# Easel_circuit_samples.net
KiCad netlist of a schematic drawn in EAGLE
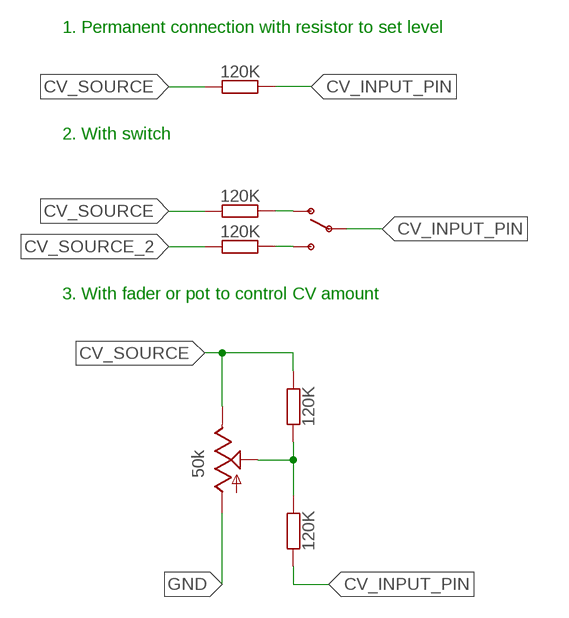
[diagram p0: schematic, sheet 1]
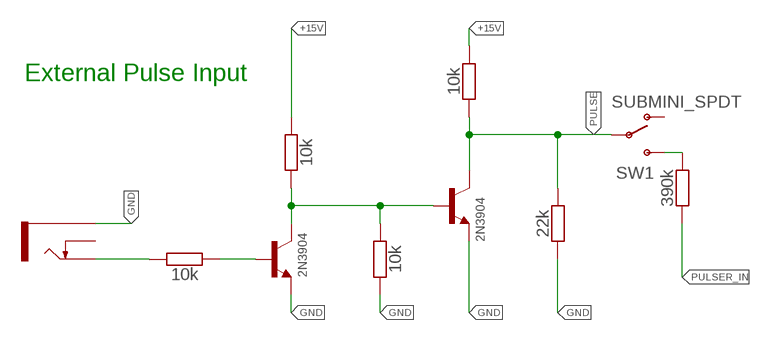
[diagram p1: schematic, sheet 2]

(export (version "E")
  (design (tool "Eeschema 10.0.6"))
  (components
    (comp (ref "Q1")
      (value "2N3904")
      (footprint "eagle-import:SC70-6")
      (libsource (lib "eagle-import") (part "TRANS_NPN_DUAL-MBT3904DW1T1"))
    )
    (comp (ref "R6")
      (value "10k")
      (footprint "eagle-import:C0603")
      (libsource (lib "eagle-import") (part "RESISTOR-0603"))
    )
    (comp (ref "R7")
      (value "10k")
      (footprint "eagle-import:C0603")
      (libsource (lib "eagle-import") (part "RESISTOR-0603"))
    )
    (comp (ref "R8")
      (value "10k")
      (footprint "eagle-import:C0603")
      (libsource (lib "eagle-import") (part "RESISTOR-0603"))
    )
    (comp (ref "R9")
      (value "10k")
      (footprint "eagle-import:C0603")
      (libsource (lib "eagle-import") (part "RESISTOR-0603"))
    )
    (comp (ref "R10")
      (value "22k")
      (footprint "eagle-import:C0603")
      (libsource (lib "eagle-import") (part "RESISTOR-0603"))
    )
    (comp (ref "R11")
      (value "390k")
      (footprint "eagle-import:C0603")
      (libsource (lib "eagle-import") (part "RESISTOR-0603"))
    )
    (comp (ref "SW1")
      (value "SUBMINI_SPDT")
      (footprint "eagle-import:SUBMINI_TOGGLE")
      (libsource (lib "eagle-import") (part "SUBMINI_SPDT"))
    )
    (comp (ref "U1")
      (value "THONKICONNNEW")
      (footprint "eagle-import:WQP-PJ301M-12_JACK")
      (libsource (lib "eagle-import") (part "THONKICONNNEW"))
    )
    (comp (ref "R1")
      (value "120K")
      (footprint "eagle-import:C0603")
      (libsource (lib "eagle-import") (part "RESISTOR-0603"))
    )
    (comp (ref "R2")
      (value "120K")
      (footprint "eagle-import:C0603")
      (libsource (lib "eagle-import") (part "RESISTOR-0603"))
    )
    (comp (ref "R3")
      (value "120K")
      (footprint "eagle-import:C0603")
      (libsource (lib "eagle-import") (part "RESISTOR-0603"))
    )
    (comp (ref "R4")
      (value "120K")
      (footprint "eagle-import:C0603")
      (libsource (lib "eagle-import") (part "RESISTOR-0603"))
    )
    (comp (ref "R5")
      (value "120K")
      (footprint "eagle-import:C0603")
      (libsource (lib "eagle-import") (part "RESISTOR-0603"))
    )
    (comp (ref "S1")
      (value "GRAYHILL_34E_SMD_TOGGLE")
      (footprint "eagle-import:34EWMSP12M6RT")
      (fields
        (field (name "ARROW_PART_NUMBER") "34EWMSP12M6RT")
        (field (name "MOUSER_PART_NUMBER") "706-34EWMSP12M6RT")
      )
      (libsource (lib "eagle-import") (part "GRAYHILL_34E_SMD_TOGGLE"))
    )
    (comp (ref "VR1")
      (value "50k")
      (footprint "eagle-import:9MM_SNAP-IN_POT")
      (libsource (lib "eagle-import") (part "9MM_SNAP-IN_POT_"))
    )
  )
  (nets
    (net (code "1") (name "+15V") (class "Default")
      (node (ref "R7") (pin "2") (pinfunction "2_2") (pintype "passive"))
      (node (ref "R9") (pin "1") (pinfunction "1_1") (pintype "passive"))
    )
    (net (code "2") (name "CV_INPUT_PIN") (class "Default")
      (node (ref "R2") (pin "1") (pinfunction "1_1") (pintype "passive"))
      (node (ref "R3") (pin "1") (pinfunction "1_1") (pintype "passive"))
      (node (ref "S1") (pin "2") (pinfunction "COMMON_2") (pintype "passive"))
    )
    (net (code "3") (name "CV_SOURCE") (class "Default")
      (node (ref "R1") (pin "2") (pinfunction "2_2") (pintype "passive"))
      (node (ref "R3") (pin "2") (pinfunction "2_2") (pintype "passive"))
      (node (ref "R4") (pin "2") (pinfunction "2_2") (pintype "passive"))
      (node (ref "VR1") (pin "3") (pinfunction "E_3") (pintype "passive"))
    )
    (net (code "4") (name "CV_SOURCE_2") (class "Default")
      (node (ref "R5") (pin "2") (pinfunction "2_2") (pintype "passive"))
    )
    (net (code "5") (name "GND") (class "Default")
      (node (ref "Q1") (pin "1") (pinfunction "E_1") (pintype "passive"))
      (node (ref "Q1") (pin "4") (pinfunction "E_4") (pintype "passive"))
      (node (ref "R10") (pin "2") (pinfunction "2_2") (pintype "passive"))
      (node (ref "R8") (pin "1") (pinfunction "1_1") (pintype "passive"))
      (node (ref "U1") (pin "P$3_SLEEVE") (pinfunction "SLEEVE_P$3_SLEEVE") (pintype "passive"))
      (node (ref "VR1") (pin "1") (pinfunction "A_1") (pintype "passive"))
    )
    (net (code "6") (name "Net-(Q1A-B)") (class "Default")
      (node (ref "Q1") (pin "5") (pinfunction "B_5") (pintype "passive"))
      (node (ref "R6") (pin "2") (pinfunction "2_2") (pintype "passive"))
    )
    (net (code "7") (name "Net-(Q1A-C)") (class "Default")
      (node (ref "Q1") (pin "2") (pinfunction "B_2") (pintype "passive"))
      (node (ref "Q1") (pin "3") (pinfunction "C_3") (pintype "passive"))
      (node (ref "R7") (pin "1") (pinfunction "1_1") (pintype "passive"))
      (node (ref "R8") (pin "2") (pinfunction "2_2") (pintype "passive"))
    )
    (net (code "8") (name "Net-(S1-O)") (class "Default")
      (node (ref "R4") (pin "1") (pinfunction "1_1") (pintype "passive"))
      (node (ref "S1") (pin "1") (pinfunction "O_1") (pintype "passive"))
    )
    (net (code "9") (name "Net-(S1-S)") (class "Default")
      (node (ref "R5") (pin "1") (pinfunction "1_1") (pintype "passive"))
      (node (ref "S1") (pin "3") (pinfunction "S_3") (pintype "passive"))
    )
    (net (code "10") (name "Net-(SW1-S)") (class "Default")
      (node (ref "R11") (pin "1") (pinfunction "1_1") (pintype "passive"))
      (node (ref "SW1") (pin "3") (pinfunction "S_3") (pintype "passive"))
    )
    (net (code "11") (name "Net-(U1-TIP)") (class "Default")
      (node (ref "R6") (pin "1") (pinfunction "1_1") (pintype "passive"))
      (node (ref "U1") (pin "P$1_TIP") (pinfunction "TIP_P$1_TIP") (pintype "passive"))
    )
    (net (code "12") (name "Net-(VR1-S)") (class "Default")
      (node (ref "R1") (pin "1") (pinfunction "1_1") (pintype "passive"))
      (node (ref "R2") (pin "2") (pinfunction "2_2") (pintype "passive"))
      (node (ref "VR1") (pin "2") (pinfunction "S_2") (pintype "passive"))
    )
    (net (code "13") (name "PULSE") (class "Default")
      (node (ref "Q1") (pin "6") (pinfunction "C_6") (pintype "passive"))
      (node (ref "R10") (pin "1") (pinfunction "1_1") (pintype "passive"))
      (node (ref "R9") (pin "2") (pinfunction "2_2") (pintype "passive"))
      (node (ref "SW1") (pin "COM") (pinfunction "COMMON_COM") (pintype "passive"))
    )
    (net (code "14") (name "PULSER_IN") (class "Default")
      (node (ref "R11") (pin "2") (pinfunction "2_2") (pintype "passive"))
    )
    (net (code "15") (name "unconnected-(SW1-O-Pad1)") (class "Default")
      (node (ref "SW1") (pin "1") (pinfunction "O_1") (pintype "passive"))
    )
    (net (code "16") (name "unconnected-(U1-SWITCH-PadP$2_SWITCH)") (class "Default")
      (node (ref "U1") (pin "P$2_SWITCH") (pinfunction "SWITCH_P$2_SWITCH") (pintype "passive"))
    )
  )
)
